# Ultrasonic.net
KiCad netlist of a schematic drawn in Altium Designer
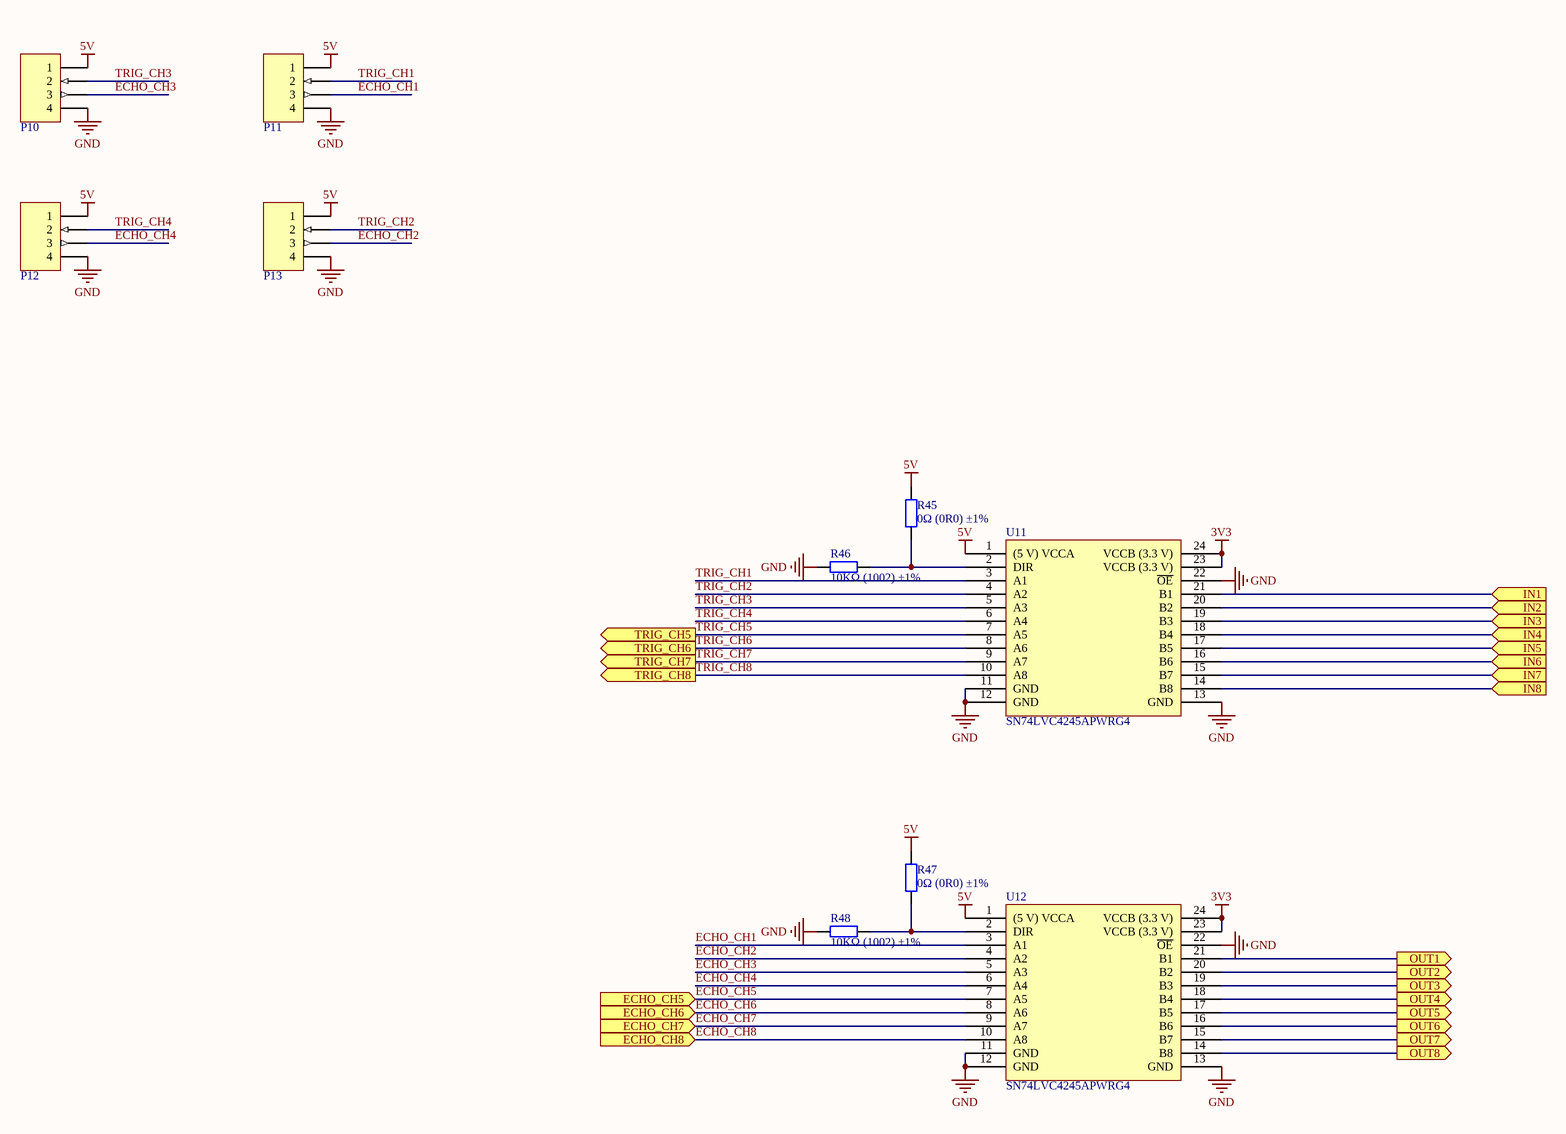
[diagram p0: Ultrasonic.SchDoc]

(export (version "E")
  (design (tool "Eeschema 10.0.6"))
  (components
    (comp (ref "P10")
      (value "B4B-PH-SM4-TB(LF)(SN)")
      (footprint "B4B-PH-SM4-TB(LF)(SN)")
      (description "CONN HEADER PH TOP 4POS 2MM SMD")
      (fields (field (name "MANUFACTURER") "JST Sales America Inc."))
      (libsource (lib "RoboteX") (part "Header 4"))
    )
    (comp (ref "P11")
      (value "B4B-PH-SM4-TB(LF)(SN)")
      (footprint "B4B-PH-SM4-TB(LF)(SN)")
      (description "CONN HEADER PH TOP 4POS 2MM SMD")
      (fields (field (name "MANUFACTURER") "JST Sales America Inc."))
      (libsource (lib "RoboteX") (part "Header 4"))
    )
    (comp (ref "P12")
      (value "B4B-PH-SM4-TB(LF)(SN)")
      (footprint "B4B-PH-SM4-TB(LF)(SN)")
      (description "CONN HEADER PH TOP 4POS 2MM SMD")
      (fields (field (name "MANUFACTURER") "JST Sales America Inc."))
      (libsource (lib "RoboteX") (part "Header 4"))
    )
    (comp (ref "P13")
      (value "B4B-PH-SM4-TB(LF)(SN)")
      (footprint "B4B-PH-SM4-TB(LF)(SN)")
      (description "CONN HEADER PH TOP 4POS 2MM SMD")
      (fields (field (name "MANUFACTURER") "JST Sales America Inc."))
      (libsource (lib "RoboteX") (part "Header 4"))
    )
    (comp (ref "R45")
      (value "0Ω (0R0) ±1%")
      (footprint "0603_R")
      (description "贴片电阻")
      (libsource (lib "Miscellaneous Devices LC") (part "0603 0Ω (0R0) 1%"))
    )
    (comp (ref "R46")
      (value "10KΩ (1002) ±1%")
      (footprint "0603_R")
      (description "贴片电阻")
      (libsource (lib "Miscellaneous Devices LC") (part "0603 10KΩ (1002) 1%"))
    )
    (comp (ref "R47")
      (value "0Ω (0R0) ±1%")
      (footprint "0603_R")
      (description "贴片电阻")
      (libsource (lib "Miscellaneous Devices LC") (part "0603 0Ω (0R0) 1%"))
    )
    (comp (ref "R48")
      (value "10KΩ (1002) ±1%")
      (footprint "0603_R")
      (description "贴片电阻")
      (libsource (lib "Miscellaneous Devices LC") (part "0603 10KΩ (1002) 1%"))
    )
    (comp (ref "U11")
      (value "SN74LVC4245APWRG4")
      (footprint "TSSOP-24")
      (description "74系列逻辑芯片")
      (libsource (lib "Miscellaneous Devices LC") (part "SN74LVC4245APWRG4_[C7859]"))
    )
    (comp (ref "U12")
      (value "SN74LVC4245APWRG4")
      (footprint "TSSOP-24")
      (description "74系列逻辑芯片")
      (libsource (lib "Miscellaneous Devices LC") (part "SN74LVC4245APWRG4_[C7859]"))
    )
  )
  (nets
    (net (code "1") (name "/ECHO_CH1") (class "Default")
      (node (ref "P11") (pin "3") (pinfunction "3_3") (pintype "output"))
      (node (ref "U12") (pin "3") (pinfunction "A1_3") (pintype "passive"))
    )
    (net (code "2") (name "/ECHO_CH2") (class "Default")
      (node (ref "P13") (pin "3") (pinfunction "3_3") (pintype "output"))
      (node (ref "U12") (pin "4") (pinfunction "A2_4") (pintype "passive"))
    )
    (net (code "3") (name "/ECHO_CH3") (class "Default")
      (node (ref "P10") (pin "3") (pinfunction "3_3") (pintype "output"))
      (node (ref "U12") (pin "5") (pinfunction "A3_5") (pintype "passive"))
    )
    (net (code "4") (name "/ECHO_CH4") (class "Default")
      (node (ref "P12") (pin "3") (pinfunction "3_3") (pintype "output"))
      (node (ref "U12") (pin "6") (pinfunction "A4_6") (pintype "passive"))
    )
    (net (code "5") (name "/ECHO_CH5") (class "Default")
      (node (ref "U12") (pin "7") (pinfunction "A5_7") (pintype "passive"))
    )
    (net (code "6") (name "/ECHO_CH6") (class "Default")
      (node (ref "U12") (pin "8") (pinfunction "A6_8") (pintype "passive"))
    )
    (net (code "7") (name "/ECHO_CH7") (class "Default")
      (node (ref "U12") (pin "9") (pinfunction "A7_9") (pintype "passive"))
    )
    (net (code "8") (name "/ECHO_CH8") (class "Default")
      (node (ref "U12") (pin "10") (pinfunction "A8_10") (pintype "passive"))
    )
    (net (code "9") (name "/IN1") (class "Default")
      (node (ref "U11") (pin "21") (pinfunction "B1_21") (pintype "passive"))
    )
    (net (code "10") (name "/IN2") (class "Default")
      (node (ref "U11") (pin "20") (pinfunction "B2_20") (pintype "passive"))
    )
    (net (code "11") (name "/IN3") (class "Default")
      (node (ref "U11") (pin "19") (pinfunction "B3_19") (pintype "passive"))
    )
    (net (code "12") (name "/IN4") (class "Default")
      (node (ref "U11") (pin "18") (pinfunction "B4_18") (pintype "passive"))
    )
    (net (code "13") (name "/IN5") (class "Default")
      (node (ref "U11") (pin "17") (pinfunction "B5_17") (pintype "passive"))
    )
    (net (code "14") (name "/IN6") (class "Default")
      (node (ref "U11") (pin "16") (pinfunction "B6_16") (pintype "passive"))
    )
    (net (code "15") (name "/IN7") (class "Default")
      (node (ref "U11") (pin "15") (pinfunction "B7_15") (pintype "passive"))
    )
    (net (code "16") (name "/IN8") (class "Default")
      (node (ref "U11") (pin "14") (pinfunction "B8_14") (pintype "passive"))
    )
    (net (code "17") (name "/OUT1") (class "Default")
      (node (ref "U12") (pin "21") (pinfunction "B1_21") (pintype "passive"))
    )
    (net (code "18") (name "/OUT2") (class "Default")
      (node (ref "U12") (pin "20") (pinfunction "B2_20") (pintype "passive"))
    )
    (net (code "19") (name "/OUT3") (class "Default")
      (node (ref "U12") (pin "19") (pinfunction "B3_19") (pintype "passive"))
    )
    (net (code "20") (name "/OUT4") (class "Default")
      (node (ref "U12") (pin "18") (pinfunction "B4_18") (pintype "passive"))
    )
    (net (code "21") (name "/OUT5") (class "Default")
      (node (ref "U12") (pin "17") (pinfunction "B5_17") (pintype "passive"))
    )
    (net (code "22") (name "/OUT6") (class "Default")
      (node (ref "U12") (pin "16") (pinfunction "B6_16") (pintype "passive"))
    )
    (net (code "23") (name "/OUT7") (class "Default")
      (node (ref "U12") (pin "15") (pinfunction "B7_15") (pintype "passive"))
    )
    (net (code "24") (name "/OUT8") (class "Default")
      (node (ref "U12") (pin "14") (pinfunction "B8_14") (pintype "passive"))
    )
    (net (code "25") (name "/TRIG_CH1") (class "Default")
      (node (ref "P11") (pin "2") (pinfunction "2_2") (pintype "input"))
      (node (ref "U11") (pin "3") (pinfunction "A1_3") (pintype "passive"))
    )
    (net (code "26") (name "/TRIG_CH2") (class "Default")
      (node (ref "P13") (pin "2") (pinfunction "2_2") (pintype "input"))
      (node (ref "U11") (pin "4") (pinfunction "A2_4") (pintype "passive"))
    )
    (net (code "27") (name "/TRIG_CH3") (class "Default")
      (node (ref "P10") (pin "2") (pinfunction "2_2") (pintype "input"))
      (node (ref "U11") (pin "5") (pinfunction "A3_5") (pintype "passive"))
    )
    (net (code "28") (name "/TRIG_CH4") (class "Default")
      (node (ref "P12") (pin "2") (pinfunction "2_2") (pintype "input"))
      (node (ref "U11") (pin "6") (pinfunction "A4_6") (pintype "passive"))
    )
    (net (code "29") (name "/TRIG_CH5") (class "Default")
      (node (ref "U11") (pin "7") (pinfunction "A5_7") (pintype "passive"))
    )
    (net (code "30") (name "/TRIG_CH6") (class "Default")
      (node (ref "U11") (pin "8") (pinfunction "A6_8") (pintype "passive"))
    )
    (net (code "31") (name "/TRIG_CH7") (class "Default")
      (node (ref "U11") (pin "9") (pinfunction "A7_9") (pintype "passive"))
    )
    (net (code "32") (name "/TRIG_CH8") (class "Default")
      (node (ref "U11") (pin "10") (pinfunction "A8_10") (pintype "passive"))
    )
    (net (code "33") (name "3V3") (class "Default")
      (node (ref "U11") (pin "23") (pinfunction "VCCB_(3.3_V)_23") (pintype "passive"))
      (node (ref "U11") (pin "24") (pinfunction "VCCB_(3.3_V)_24") (pintype "passive"))
      (node (ref "U12") (pin "23") (pinfunction "VCCB_(3.3_V)_23") (pintype "passive"))
      (node (ref "U12") (pin "24") (pinfunction "VCCB_(3.3_V)_24") (pintype "passive"))
    )
    (net (code "34") (name "5V") (class "Default")
      (node (ref "P10") (pin "1") (pinfunction "1_1") (pintype "passive"))
      (node (ref "P11") (pin "1") (pinfunction "1_1") (pintype "passive"))
      (node (ref "P12") (pin "1") (pinfunction "1_1") (pintype "passive"))
      (node (ref "P13") (pin "1") (pinfunction "1_1") (pintype "passive"))
      (node (ref "R45") (pin "2") (pinfunction "2_2") (pintype "passive"))
      (node (ref "R47") (pin "2") (pinfunction "2_2") (pintype "passive"))
      (node (ref "U11") (pin "1") (pinfunction "(5_V)_VCCA_1") (pintype "passive"))
      (node (ref "U12") (pin "1") (pinfunction "(5_V)_VCCA_1") (pintype "passive"))
    )
    (net (code "35") (name "GND") (class "Default")
      (node (ref "P10") (pin "4") (pinfunction "4_4") (pintype "passive"))
      (node (ref "P11") (pin "4") (pinfunction "4_4") (pintype "passive"))
      (node (ref "P12") (pin "4") (pinfunction "4_4") (pintype "passive"))
      (node (ref "P13") (pin "4") (pinfunction "4_4") (pintype "passive"))
      (node (ref "R46") (pin "1") (pinfunction "1_1") (pintype "passive"))
      (node (ref "R48") (pin "1") (pinfunction "1_1") (pintype "passive"))
      (node (ref "U11") (pin "11") (pinfunction "GND_11") (pintype "passive"))
      (node (ref "U11") (pin "12") (pinfunction "GND_12") (pintype "passive"))
      (node (ref "U11") (pin "13") (pinfunction "GND_13") (pintype "passive"))
      (node (ref "U11") (pin "22") (pinfunction "~{OE}_22") (pintype "passive"))
      (node (ref "U12") (pin "11") (pinfunction "GND_11") (pintype "passive"))
      (node (ref "U12") (pin "12") (pinfunction "GND_12") (pintype "passive"))
      (node (ref "U12") (pin "13") (pinfunction "GND_13") (pintype "passive"))
      (node (ref "U12") (pin "22") (pinfunction "~{OE}_22") (pintype "passive"))
    )
    (net (code "36") (name "Net-(U11-DIR)") (class "Default")
      (node (ref "R45") (pin "1") (pinfunction "1_1") (pintype "passive"))
      (node (ref "R46") (pin "2") (pinfunction "2_2") (pintype "passive"))
      (node (ref "U11") (pin "2") (pinfunction "DIR_2") (pintype "passive"))
    )
    (net (code "37") (name "Net-(U12-DIR)") (class "Default")
      (node (ref "R47") (pin "1") (pinfunction "1_1") (pintype "passive"))
      (node (ref "R48") (pin "2") (pinfunction "2_2") (pintype "passive"))
      (node (ref "U12") (pin "2") (pinfunction "DIR_2") (pintype "passive"))
    )
  )
)
